# SolidStateRadiationChannel.net
KiCad netlist of a schematic drawn in Altium Designer
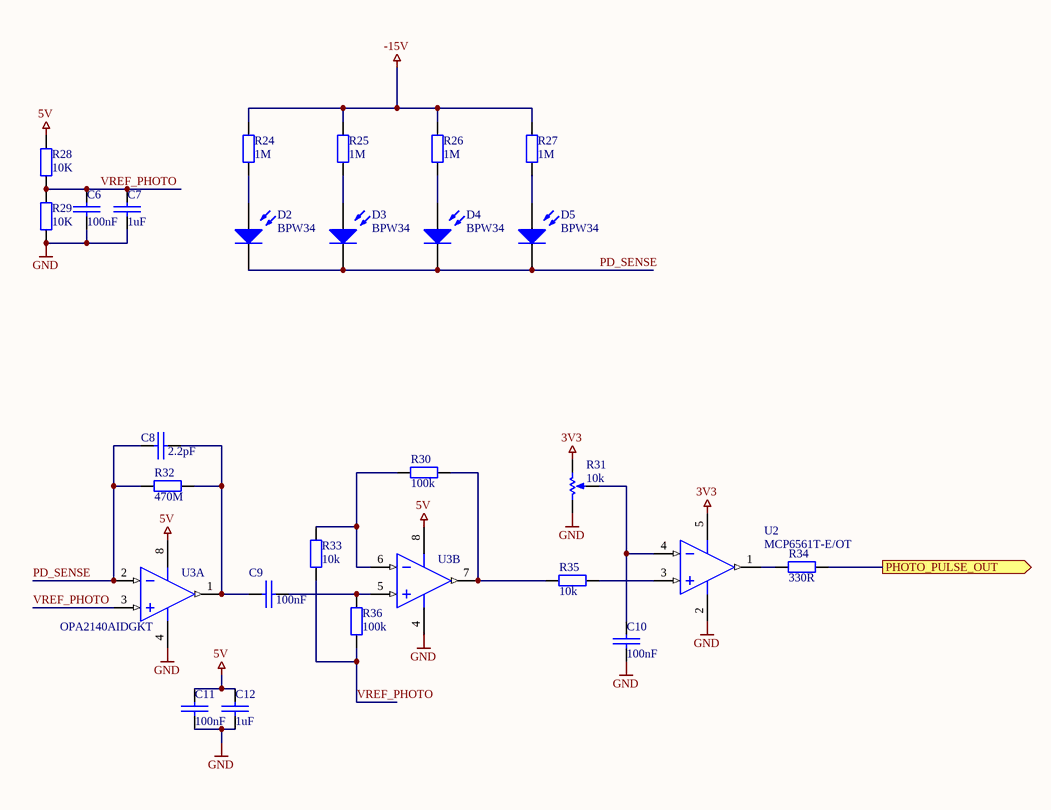
[diagram p0: SolidStateRadiationChannel.SchDoc]

(export (version "E")
  (design (tool "Eeschema 10.0.6"))
  (components
    (comp (ref "C6") (value "100nF") (footprint "Cap_0805") (libsource (lib "*") (part "C")))
    (comp (ref "C7") (value "1uF") (footprint "Cap_0805") (libsource (lib "*") (part "C")))
    (comp (ref "C8") (value "2.2pF") (footprint "Cap_0805") (libsource (lib "*") (part "C")))
    (comp (ref "C9") (value "100nF") (footprint "Cap_0805") (libsource (lib "*") (part "C")))
    (comp (ref "C10") (value "100nF") (footprint "Cap_0805") (libsource (lib "*") (part "C")))
    (comp (ref "C11") (value "100nF") (footprint "Cap_0805") (libsource (lib "*") (part "C")))
    (comp (ref "C12") (value "1uF") (footprint "Cap_0805") (libsource (lib "*") (part "C")))
    (comp (ref "D2")
      (value "BPW34")
      (footprint "BPW34")
      (description "Silicon PIN Photodiode")
      (libsource (lib "AZR-LIB") (part "BPW34"))
    )
    (comp (ref "D3")
      (value "BPW34")
      (footprint "BPW34")
      (description "Silicon PIN Photodiode")
      (libsource (lib "AZR-LIB") (part "BPW34"))
    )
    (comp (ref "D4")
      (value "BPW34")
      (footprint "BPW34")
      (description "Silicon PIN Photodiode")
      (libsource (lib "AZR-LIB") (part "BPW34"))
    )
    (comp (ref "D5")
      (value "BPW34")
      (footprint "BPW34")
      (description "Silicon PIN Photodiode")
      (libsource (lib "AZR-LIB") (part "BPW34"))
    )
    (comp (ref "R24")
      (value "1M")
      (footprint "RES_0805")
      (description "Res 0805")
      (fields (field (name "PART NUMBER") "ERJ6ENF2703V") (field (name "MANUFACTURER") "Panasonic"))
      (libsource (lib "2121_Robot3roues_V2.0") (part "RES"))
    )
    (comp (ref "R25")
      (value "1M")
      (footprint "RES_0805")
      (description "Res 0805")
      (fields (field (name "PART NUMBER") "ERJ6ENF2703V") (field (name "MANUFACTURER") "Panasonic"))
      (libsource (lib "2121_Robot3roues_V2.0") (part "RES"))
    )
    (comp (ref "R26")
      (value "1M")
      (footprint "RES_0805")
      (description "Res 0805")
      (fields (field (name "PART NUMBER") "ERJ6ENF2703V") (field (name "MANUFACTURER") "Panasonic"))
      (libsource (lib "2121_Robot3roues_V2.0") (part "RES"))
    )
    (comp (ref "R27")
      (value "1M")
      (footprint "RES_0805")
      (description "Res 0805")
      (fields (field (name "PART NUMBER") "ERJ6ENF2703V") (field (name "MANUFACTURER") "Panasonic"))
      (libsource (lib "2121_Robot3roues_V2.0") (part "RES"))
    )
    (comp (ref "R28")
      (value "10K")
      (footprint "RES_0805")
      (description "Res 0805")
      (fields (field (name "PART NUMBER") "ERJ6ENF2703V") (field (name "MANUFACTURER") "Panasonic"))
      (libsource (lib "2121_Robot3roues_V2.0") (part "RES"))
    )
    (comp (ref "R29")
      (value "10K")
      (footprint "RES_0805")
      (description "Res 0805")
      (fields (field (name "PART NUMBER") "ERJ6ENF2703V") (field (name "MANUFACTURER") "Panasonic"))
      (libsource (lib "2121_Robot3roues_V2.0") (part "RES"))
    )
    (comp (ref "R30")
      (value "100k")
      (footprint "RES_0805")
      (description "Res 0805")
      (fields (field (name "PART NUMBER") "ERJ6ENF2703V") (field (name "MANUFACTURER") "Panasonic"))
      (libsource (lib "") (part "RES_1"))
    )
    (comp (ref "R31")
      (value "10k")
      (footprint "VR5")
      (description "Potentiometer")
      (fields (field (name "PUBLISHER") "Altium Limited"))
      (libsource (lib "Miscellaneous Devices") (part "RPot"))
    )
    (comp (ref "R32")
      (value "470M")
      (footprint "RES_0805")
      (description "Res 0805")
      (fields (field (name "PART NUMBER") "ERJ6ENF2703V") (field (name "MANUFACTURER") "Panasonic"))
      (libsource (lib "") (part "RES_1"))
    )
    (comp (ref "R33")
      (value "10k")
      (footprint "RES_0805")
      (description "Res 0805")
      (fields (field (name "PART NUMBER") "ERJ6ENF2703V") (field (name "MANUFACTURER") "Panasonic"))
      (libsource (lib "2121_Robot3roues_V2.0") (part "RES"))
    )
    (comp (ref "R34")
      (value "330R")
      (footprint "RES_0805")
      (description "Res 0805")
      (fields (field (name "PART NUMBER") "ERJ6ENF2703V") (field (name "MANUFACTURER") "Panasonic"))
      (libsource (lib "") (part "RES_1"))
    )
    (comp (ref "R35")
      (value "10k")
      (footprint "RES_0805")
      (description "Res 0805")
      (fields (field (name "PART NUMBER") "ERJ6ENF2703V") (field (name "MANUFACTURER") "Panasonic"))
      (libsource (lib "") (part "RES_1"))
    )
    (comp (ref "R36")
      (value "100k")
      (footprint "RES_0805")
      (description "Res 0805")
      (fields (field (name "PART NUMBER") "ERJ6ENF2703V") (field (name "MANUFACTURER") "Panasonic"))
      (libsource (lib "2121_Robot3roues_V2.0") (part "RES"))
    )
    (comp (ref "U2")
      (value "MCP6561T-E/OT")
      (footprint "SOT-23-OT5_L")
      (description "None")
      (libsource (lib "Altium Content Vault") (part "LO-COMP-MCP6561-SOT5"))
    )
    (comp (ref "U3")
      (value "OPA2140AIDGKT")
      (footprint "DGK0008A_N")
      (fields (field (name "MANUFACTURER") "Texas Instruments"))
      (libsource (lib "Altium Content Vault") (part "TI-OPA-8_2"))
    )
  )
  (nets
    (net (code "1") (name "-15V") (class "Default")
      (node (ref "R24") (pin "1") (pinfunction "1_1") (pintype "passive"))
      (node (ref "R25") (pin "1") (pinfunction "1_1") (pintype "passive"))
      (node (ref "R26") (pin "1") (pinfunction "1_1") (pintype "passive"))
      (node (ref "R27") (pin "1") (pinfunction "1_1") (pintype "passive"))
    )
    (net (code "2") (name "/PD_SENSE") (class "Default")
      (node (ref "C8") (pin "1") (pinfunction "1_1") (pintype "passive"))
      (node (ref "D2") (pin "2") (pinfunction "K_2") (pintype "passive"))
      (node (ref "D3") (pin "2") (pinfunction "K_2") (pintype "passive"))
      (node (ref "D4") (pin "2") (pinfunction "K_2") (pintype "passive"))
      (node (ref "D5") (pin "2") (pinfunction "K_2") (pintype "passive"))
      (node (ref "R32") (pin "1") (pinfunction "1_1") (pintype "passive"))
      (node (ref "U3") (pin "2") (pinfunction "IN_A-_2") (pintype "input"))
    )
    (net (code "3") (name "/PHOTO_PULSE_OUT") (class "Default")
      (node (ref "R34") (pin "2") (pinfunction "2_2") (pintype "passive"))
    )
    (net (code "4") (name "/VREF_PHOTO") (class "Default")
      (node (ref "C6") (pin "1") (pinfunction "1_1") (pintype "passive"))
      (node (ref "C7") (pin "1") (pinfunction "1_1") (pintype "passive"))
      (node (ref "R28") (pin "2") (pinfunction "2_2") (pintype "passive"))
      (node (ref "R29") (pin "1") (pinfunction "1_1") (pintype "passive"))
      (node (ref "R33") (pin "2") (pinfunction "2_2") (pintype "passive"))
      (node (ref "R36") (pin "2") (pinfunction "2_2") (pintype "passive"))
      (node (ref "U3") (pin "3") (pinfunction "IN_A+_3") (pintype "input"))
    )
    (net (code "5") (name "3V3") (class "Default")
      (node (ref "R31") (pin "1") (pinfunction "TOP_1") (pintype "passive"))
      (node (ref "U2") (pin "5") (pinfunction "VDD_5") (pintype "power_in"))
    )
    (net (code "6") (name "5V") (class "Default")
      (node (ref "C11") (pin "1") (pinfunction "1_1") (pintype "passive"))
      (node (ref "C12") (pin "1") (pinfunction "1_1") (pintype "passive"))
      (node (ref "R28") (pin "1") (pinfunction "1_1") (pintype "passive"))
      (node (ref "U3") (pin "8") (pinfunction "V+_8") (pintype "power_in"))
    )
    (net (code "7") (name "GND") (class "Default")
      (node (ref "C10") (pin "1") (pinfunction "1_1") (pintype "passive"))
      (node (ref "C11") (pin "2") (pinfunction "2_2") (pintype "passive"))
      (node (ref "C12") (pin "2") (pinfunction "2_2") (pintype "passive"))
      (node (ref "C6") (pin "2") (pinfunction "2_2") (pintype "passive"))
      (node (ref "C7") (pin "2") (pinfunction "2_2") (pintype "passive"))
      (node (ref "R29") (pin "2") (pinfunction "2_2") (pintype "passive"))
      (node (ref "R31") (pin "2") (pinfunction "BOT_2") (pintype "passive"))
      (node (ref "U2") (pin "2") (pinfunction "VSS_2") (pintype "power_in"))
      (node (ref "U3") (pin "4") (pinfunction "V-_4") (pintype "power_in"))
    )
    (net (code "8") (name "Net-(D2-A)") (class "Default")
      (node (ref "D2") (pin "1") (pinfunction "A_1") (pintype "passive"))
      (node (ref "R24") (pin "2") (pinfunction "2_2") (pintype "passive"))
    )
    (net (code "9") (name "Net-(D3-A)") (class "Default")
      (node (ref "D3") (pin "1") (pinfunction "A_1") (pintype "passive"))
      (node (ref "R25") (pin "2") (pinfunction "2_2") (pintype "passive"))
    )
    (net (code "10") (name "Net-(D4-A)") (class "Default")
      (node (ref "D4") (pin "1") (pinfunction "A_1") (pintype "passive"))
      (node (ref "R26") (pin "2") (pinfunction "2_2") (pintype "passive"))
    )
    (net (code "11") (name "Net-(D5-A)") (class "Default")
      (node (ref "D5") (pin "1") (pinfunction "A_1") (pintype "passive"))
      (node (ref "R27") (pin "2") (pinfunction "2_2") (pintype "passive"))
    )
    (net (code "12") (name "Net-(R31-TAP)") (class "Default")
      (node (ref "C10") (pin "2") (pinfunction "2_2") (pintype "passive"))
      (node (ref "R31") (pin "3") (pinfunction "TAP_3") (pintype "passive"))
      (node (ref "U2") (pin "4") (pinfunction "IN-_4") (pintype "input"))
    )
    (net (code "13") (name "Net-(U2-IN+)") (class "Default")
      (node (ref "R35") (pin "2") (pinfunction "2_2") (pintype "passive"))
      (node (ref "U2") (pin "3") (pinfunction "IN+_3") (pintype "input"))
    )
    (net (code "14") (name "Net-(U2-OUT)") (class "Default")
      (node (ref "R34") (pin "1") (pinfunction "1_1") (pintype "passive"))
      (node (ref "U2") (pin "1") (pinfunction "OUT_1") (pintype "output"))
    )
    (net (code "15") (name "Net-(U3A-OUT_A)") (class "Default")
      (node (ref "C8") (pin "2") (pinfunction "2_2") (pintype "passive"))
      (node (ref "C9") (pin "1") (pinfunction "1_1") (pintype "passive"))
      (node (ref "R32") (pin "2") (pinfunction "2_2") (pintype "passive"))
      (node (ref "U3") (pin "1") (pinfunction "OUT_A_1") (pintype "output"))
    )
    (net (code "16") (name "Net-(U3B-IN_B+)") (class "Default")
      (node (ref "C9") (pin "2") (pinfunction "2_2") (pintype "passive"))
      (node (ref "R36") (pin "1") (pinfunction "1_1") (pintype "passive"))
      (node (ref "U3") (pin "5") (pinfunction "IN_B+_5") (pintype "input"))
    )
    (net (code "17") (name "Net-(U3B-IN_B-)") (class "Default")
      (node (ref "R30") (pin "1") (pinfunction "1_1") (pintype "passive"))
      (node (ref "R33") (pin "1") (pinfunction "1_1") (pintype "passive"))
      (node (ref "U3") (pin "6") (pinfunction "IN_B-_6") (pintype "input"))
    )
    (net (code "18") (name "Net-(U3B-OUT_B)") (class "Default")
      (node (ref "R30") (pin "2") (pinfunction "2_2") (pintype "passive"))
      (node (ref "R35") (pin "1") (pinfunction "1_1") (pintype "passive"))
      (node (ref "U3") (pin "7") (pinfunction "OUT_B_7") (pintype "output"))
    )
  )
)
